# EEPROM-protowiring.net
KiCad netlist of a schematic drawn in EAGLE
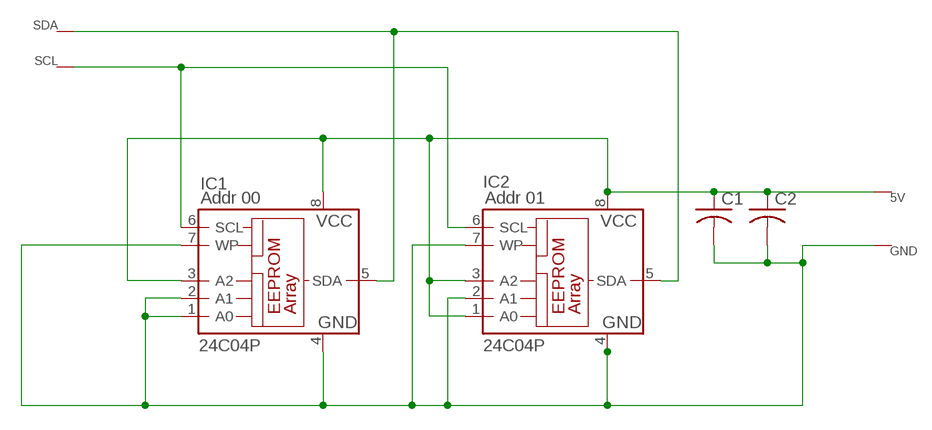
[diagram p0: schematic, sheet 1]

(export (version "E")
  (design (tool "Eeschema 10.0.6"))
  (components
    (comp (ref "5V")
      (value "WIRE-VIA8")
      (footprint "eagle-import:VIA8")
      (libsource (lib "eagle-import") (part "WIRE-VIA8"))
    )
    (comp (ref "C1")
      (value "C-US-2.5MM")
      (footprint "eagle-import:C025-025X050")
      (libsource (lib "eagle-import") (part "C-US-2.5MM"))
    )
    (comp (ref "C2")
      (value "C-US-2.5MM")
      (footprint "eagle-import:C025-025X050")
      (libsource (lib "eagle-import") (part "C-US-2.5MM"))
    )
    (comp (ref "GND")
      (value "WIRE-VIA8")
      (footprint "eagle-import:VIA8")
      (libsource (lib "eagle-import") (part "WIRE-VIA8"))
    )
    (comp (ref "IC1")
      (value "24C04P")
      (footprint "eagle-import:DIL8")
      (fields (field (name "MPN") "M24C04-WBN6P"))
      (libsource (lib "eagle-import") (part "24CP04"))
    )
    (comp (ref "IC2")
      (value "24C04P")
      (footprint "eagle-import:DIL8")
      (fields (field (name "MPN") "M24C04-WBN6P"))
      (libsource (lib "eagle-import") (part "24CP04"))
    )
    (comp (ref "SCL")
      (value "WIRE-VIA8")
      (footprint "eagle-import:VIA8")
      (libsource (lib "eagle-import") (part "WIRE-VIA8"))
    )
    (comp (ref "SDA")
      (value "WIRE-VIA8")
      (footprint "eagle-import:VIA8")
      (libsource (lib "eagle-import") (part "WIRE-VIA8"))
    )
  )
  (nets
    (net (code "1") (name "Net-(IC1-A0)") (class "Default")
      (node (ref "C1") (pin "2") (pinfunction "2_2") (pintype "passive"))
      (node (ref "C2") (pin "2") (pinfunction "2_2") (pintype "passive"))
      (node (ref "GND") (pin "P$1") (pinfunction "P$1_P$1") (pintype "bidirectional"))
      (node (ref "IC1") (pin "1") (pinfunction "A0_1") (pintype "input"))
      (node (ref "IC1") (pin "2") (pinfunction "A1_2") (pintype "input"))
      (node (ref "IC1") (pin "4") (pinfunction "GND_4") (pintype "power_in"))
      (node (ref "IC1") (pin "7") (pinfunction "WP_7") (pintype "input"))
      (node (ref "IC2") (pin "2") (pinfunction "A1_2") (pintype "input"))
      (node (ref "IC2") (pin "4") (pinfunction "GND_4") (pintype "power_in"))
      (node (ref "IC2") (pin "7") (pinfunction "WP_7") (pintype "input"))
    )
    (net (code "2") (name "Net-(IC1-A2)") (class "Default")
      (node (ref "5V") (pin "P$1") (pinfunction "P$1_P$1") (pintype "bidirectional"))
      (node (ref "C1") (pin "1") (pinfunction "1_1") (pintype "passive"))
      (node (ref "C2") (pin "1") (pinfunction "1_1") (pintype "passive"))
      (node (ref "IC1") (pin "3") (pinfunction "A2_3") (pintype "input"))
      (node (ref "IC1") (pin "8") (pinfunction "VCC_8") (pintype "power_in"))
      (node (ref "IC2") (pin "1") (pinfunction "A0_1") (pintype "input"))
      (node (ref "IC2") (pin "3") (pinfunction "A2_3") (pintype "input"))
      (node (ref "IC2") (pin "8") (pinfunction "VCC_8") (pintype "power_in"))
    )
    (net (code "3") (name "Net-(IC1-SCL)") (class "Default")
      (node (ref "IC1") (pin "6") (pinfunction "SCL_6") (pintype "input"))
      (node (ref "IC2") (pin "6") (pinfunction "SCL_6") (pintype "input"))
      (node (ref "SCL") (pin "P$1") (pinfunction "P$1_P$1") (pintype "bidirectional"))
    )
    (net (code "4") (name "Net-(IC1-SDA)") (class "Default")
      (node (ref "IC1") (pin "5") (pinfunction "SDA_5") (pintype "bidirectional"))
      (node (ref "IC2") (pin "5") (pinfunction "SDA_5") (pintype "bidirectional"))
      (node (ref "SDA") (pin "P$1") (pinfunction "P$1_P$1") (pintype "bidirectional"))
    )
  )
)
